# fieldkit-upper.net
KiCad netlist of a schematic drawn in EAGLE
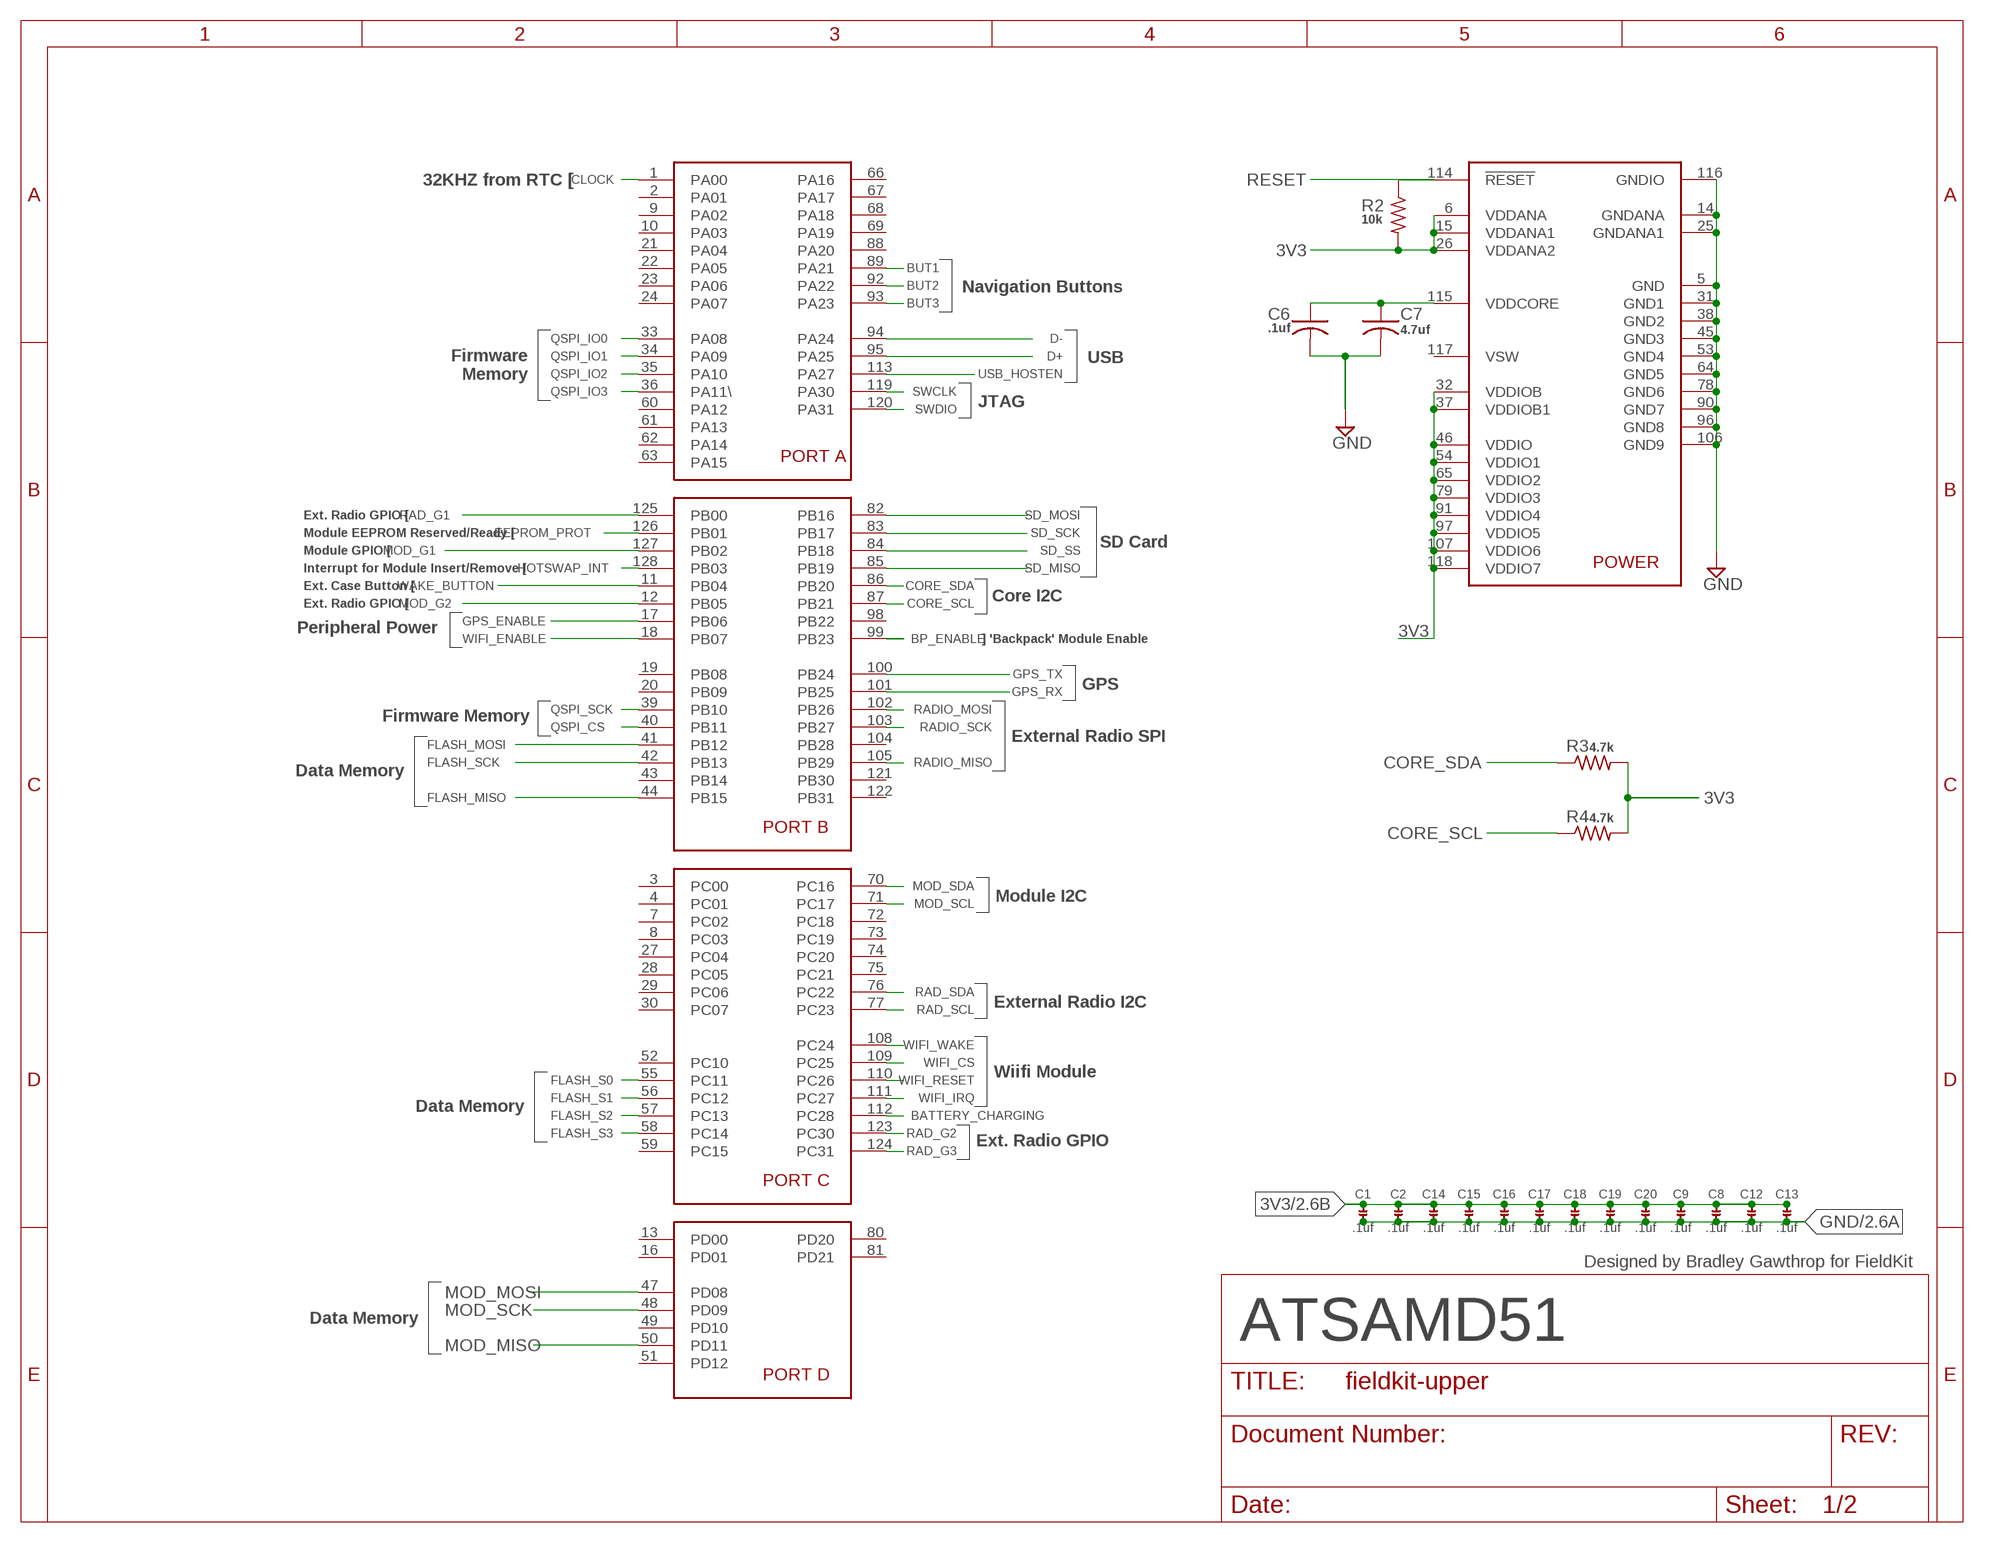
[diagram p0: schematic, sheet 1]
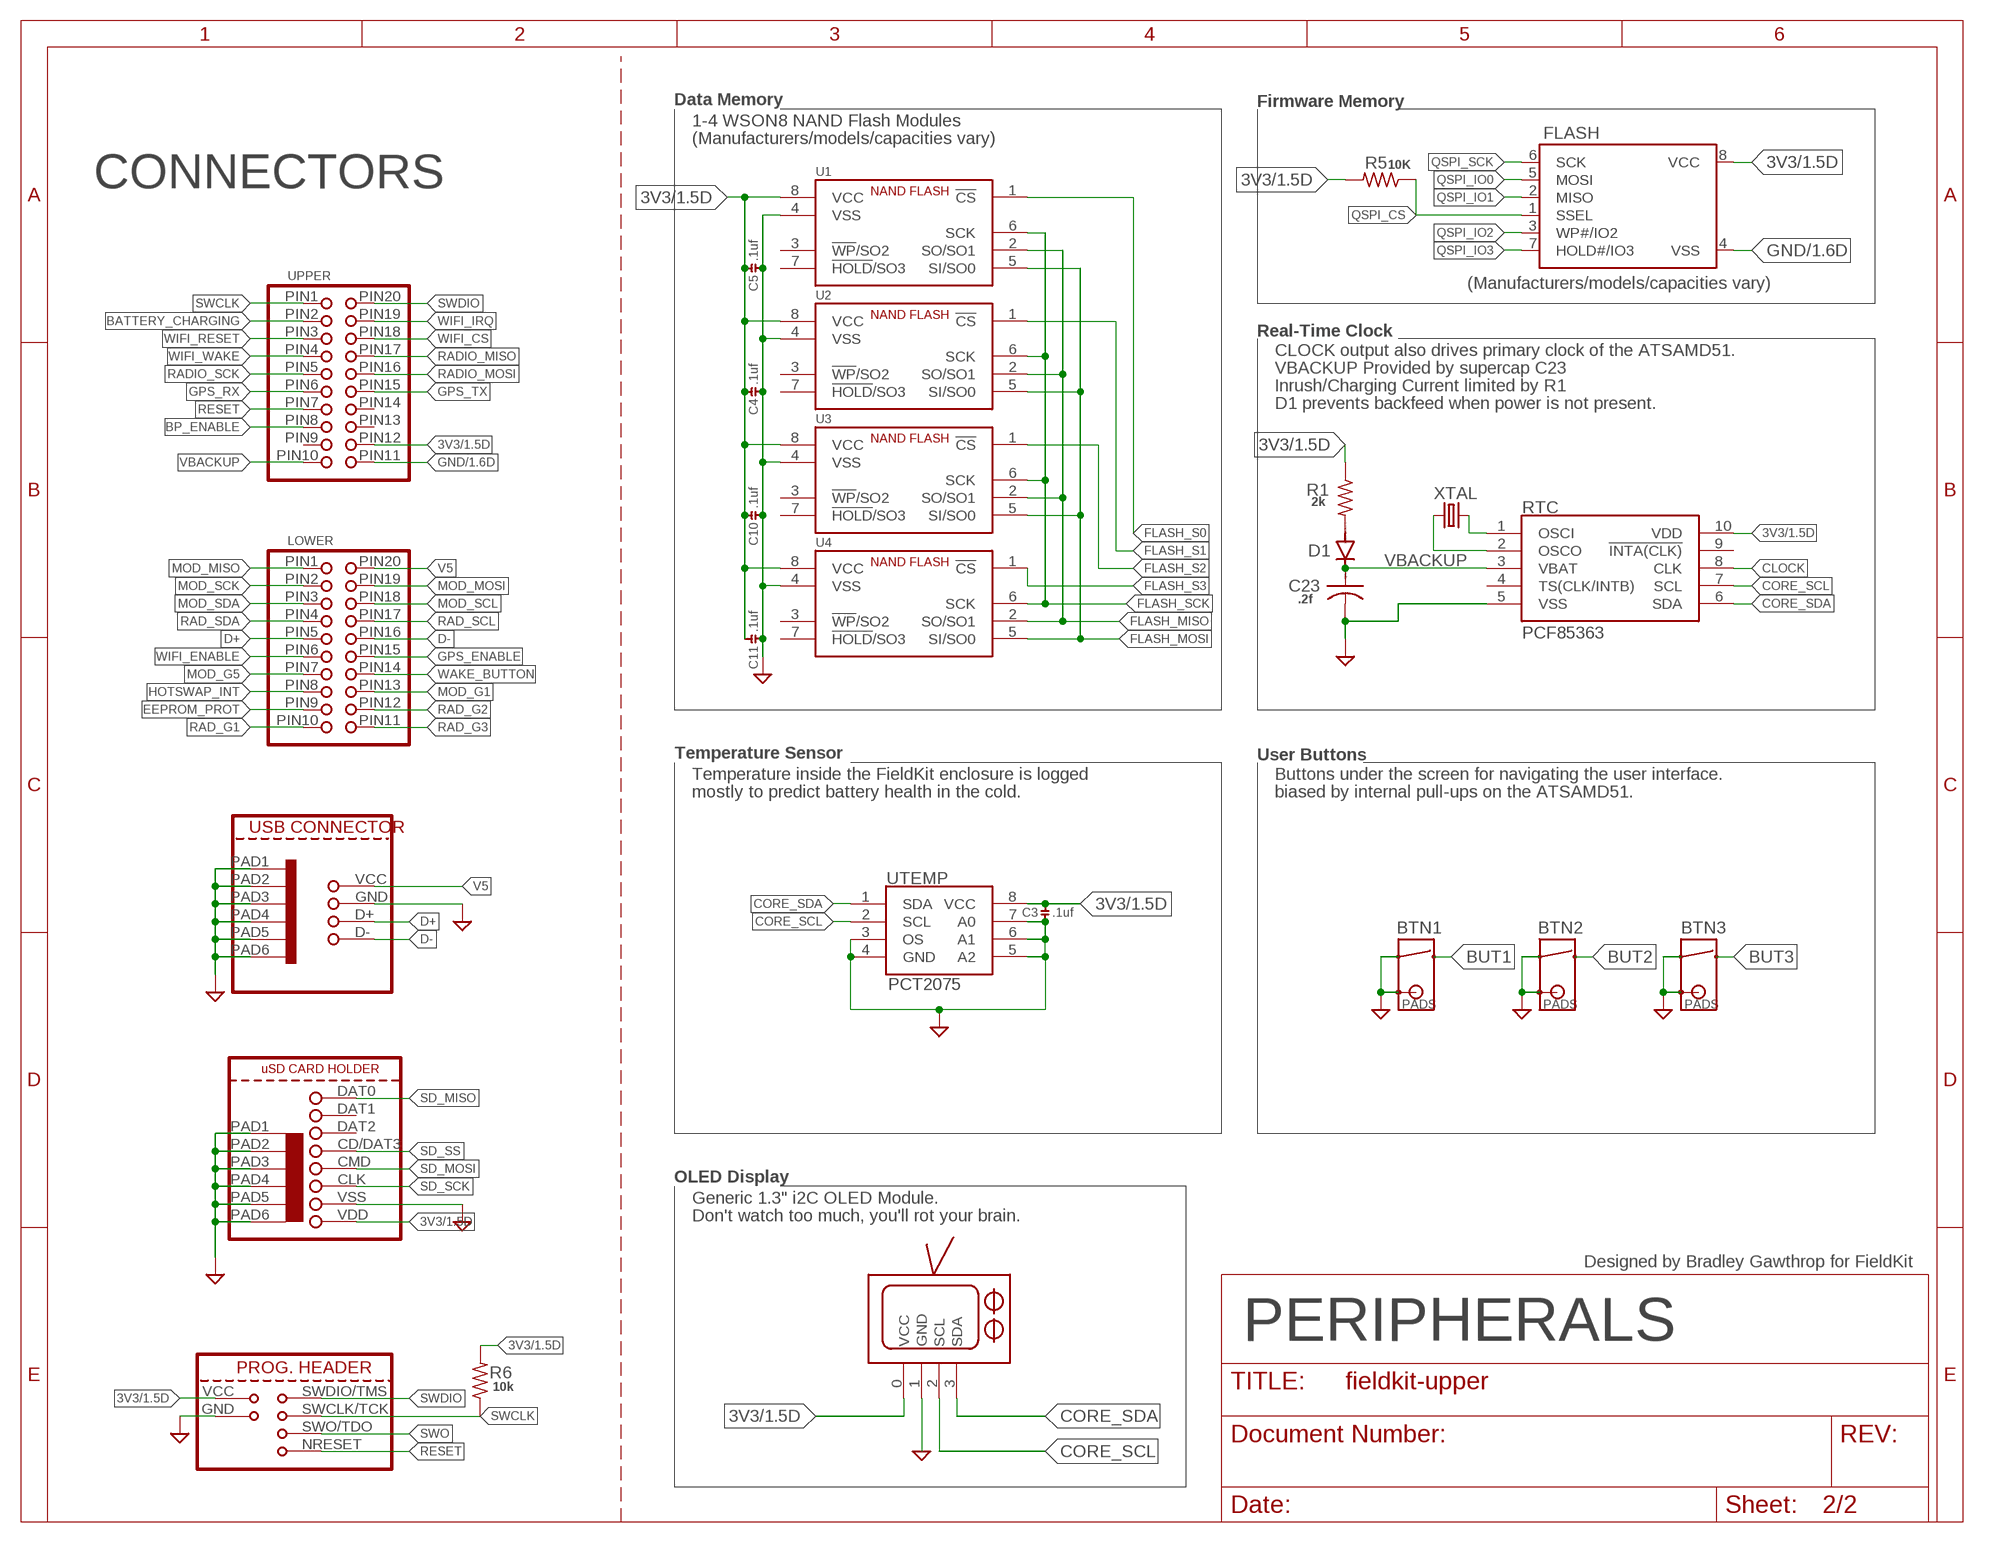
[diagram p1: schematic, sheet 2]

(export (version "E")
  (design (tool "Eeschema 10.0.6"))
  (components
    (comp (ref "BRAIN")
      (value "SAMD51PXXA")
      (footprint "eagle-import:SQFP-S-14X14-128")
      (libsource (lib "eagle-import") (part "SAMD51PXXA"))
    )
    (comp (ref "C1")
      (value ".1uf")
      (footprint "eagle-import:C0603K")
      (libsource (lib "eagle-import") (part "DCAP"))
    )
    (comp (ref "C2")
      (value ".1uf")
      (footprint "eagle-import:C0603K")
      (libsource (lib "eagle-import") (part "DCAP"))
    )
    (comp (ref "C6")
      (value ".1uf")
      (footprint "eagle-import:C0603K")
      (libsource (lib "eagle-import") (part "C-USC0603K"))
    )
    (comp (ref "C7")
      (value "4.7uf")
      (footprint "eagle-import:C0603K")
      (libsource (lib "eagle-import") (part "C-USC0603K"))
    )
    (comp (ref "C8")
      (value ".1uf")
      (footprint "eagle-import:C0603K")
      (libsource (lib "eagle-import") (part "DCAP"))
    )
    (comp (ref "C9")
      (value ".1uf")
      (footprint "eagle-import:C0603K")
      (libsource (lib "eagle-import") (part "DCAP"))
    )
    (comp (ref "C12")
      (value ".1uf")
      (footprint "eagle-import:C0603K")
      (libsource (lib "eagle-import") (part "DCAP"))
    )
    (comp (ref "C13")
      (value ".1uf")
      (footprint "eagle-import:C0603K")
      (libsource (lib "eagle-import") (part "DCAP"))
    )
    (comp (ref "C14")
      (value ".1uf")
      (footprint "eagle-import:C0603K")
      (libsource (lib "eagle-import") (part "DCAP"))
    )
    (comp (ref "C15")
      (value ".1uf")
      (footprint "eagle-import:C0603K")
      (libsource (lib "eagle-import") (part "DCAP"))
    )
    (comp (ref "C16")
      (value ".1uf")
      (footprint "eagle-import:C0603K")
      (libsource (lib "eagle-import") (part "DCAP"))
    )
    (comp (ref "C17")
      (value ".1uf")
      (footprint "eagle-import:C0603K")
      (libsource (lib "eagle-import") (part "DCAP"))
    )
    (comp (ref "C18")
      (value ".1uf")
      (footprint "eagle-import:C0603K")
      (libsource (lib "eagle-import") (part "DCAP"))
    )
    (comp (ref "C19")
      (value ".1uf")
      (footprint "eagle-import:C0603K")
      (libsource (lib "eagle-import") (part "DCAP"))
    )
    (comp (ref "C20")
      (value ".1uf")
      (footprint "eagle-import:C0603K")
      (libsource (lib "eagle-import") (part "DCAP"))
    )
    (comp (ref "R2")
      (value "10k")
      (footprint "eagle-import:R0603")
      (libsource (lib "eagle-import") (part "R-US_R0603"))
    )
    (comp (ref "R3")
      (value "4.7k")
      (footprint "eagle-import:R0603")
      (libsource (lib "eagle-import") (part "R-US_R0603"))
    )
    (comp (ref "R4")
      (value "4.7k")
      (footprint "eagle-import:R0603")
      (libsource (lib "eagle-import") (part "R-US_R0603"))
    )
    (comp (ref "BTN1")
      (value "SKRTLAE010")
      (footprint "eagle-import:SKRTLAE010")
      (libsource (lib "eagle-import") (part "SKRTLAE010"))
    )
    (comp (ref "BTN2")
      (value "SKRTLAE010")
      (footprint "eagle-import:SKRTLAE010")
      (libsource (lib "eagle-import") (part "SKRTLAE010"))
    )
    (comp (ref "BTN3")
      (value "SKRTLAE010")
      (footprint "eagle-import:SKRTLAE010")
      (libsource (lib "eagle-import") (part "SKRTLAE010"))
    )
    (comp (ref "C3")
      (value ".1uf")
      (footprint "eagle-import:C0603K")
      (libsource (lib "eagle-import") (part "DCAP"))
    )
    (comp (ref "C4")
      (value ".1uf")
      (footprint "eagle-import:C0603K")
      (libsource (lib "eagle-import") (part "DCAP"))
    )
    (comp (ref "C5")
      (value ".1uf")
      (footprint "eagle-import:C0603K")
      (libsource (lib "eagle-import") (part "DCAP"))
    )
    (comp (ref "C10")
      (value ".1uf")
      (footprint "eagle-import:C0603K")
      (libsource (lib "eagle-import") (part "DCAP"))
    )
    (comp (ref "C11")
      (value ".1uf")
      (footprint "eagle-import:C0603K")
      (libsource (lib "eagle-import") (part "DCAP"))
    )
    (comp (ref "C23")
      (value ".2f")
      (footprint "eagle-import:SUPERCAP")
      (libsource (lib "eagle-import") (part "DSK-3R3H204T614-H2L"))
    )
    (comp (ref "D1")
      (value "VS-10BQ015HM3/5BT")
      (footprint "eagle-import:SMB")
      (libsource (lib "eagle-import") (part "DIODE-SMB"))
    )
    (comp (ref "FLASH")
      (value "SPIFLASH_SOIC8208MIL")
      (footprint "eagle-import:SOIC8_208MIL")
      (libsource (lib "eagle-import") (part "SPIFLASH_SOIC8208MIL"))
    )
    (comp (ref "J1")
      (value "TAG-CONNECT")
      (footprint "eagle-import:TC2030-IDC")
      (libsource (lib "eagle-import") (part "TAG-CONNECT"))
    )
    (comp (ref "LOWER")
      (value "MOLEX-15-91-2200F")
      (footprint "eagle-import:20PH-F")
      (libsource (lib "eagle-import") (part "MOLEX-15-91-2200F"))
    )
    (comp (ref "R1")
      (value "2k")
      (footprint "eagle-import:R0603")
      (libsource (lib "eagle-import") (part "R-US_R0603"))
    )
    (comp (ref "R5")
      (value "10K")
      (footprint "eagle-import:R0603")
      (libsource (lib "eagle-import") (part "R-US_R0603"))
    )
    (comp (ref "R6")
      (value "10k")
      (footprint "eagle-import:R0603")
      (libsource (lib "eagle-import") (part "R-US_R0603"))
    )
    (comp (ref "RTC")
      (value "PCF85363ATT")
      (footprint "eagle-import:SOP50P490X110-10")
      (libsource (lib "eagle-import") (part "PCF85363ATT"))
    )
    (comp (ref "SCREEN")
      (value "SCREEN")
      (footprint "eagle-import:SCREEN")
      (libsource (lib "eagle-import") (part "SCREEN"))
    )
    (comp (ref "SD")
      (value "DM3D-SF")
      (footprint "eagle-import:DM3D-SF")
      (libsource (lib "eagle-import") (part "DM3D-SF"))
    )
    (comp (ref "U1")
      (value "TC58CVG1S3HRAIG")
      (footprint "eagle-import:WSON8")
      (libsource (lib "eagle-import") (part "TC58CVG1S3HRAIG"))
    )
    (comp (ref "U2")
      (value "TC58CVG1S3HRAIG")
      (footprint "eagle-import:WSON8")
      (libsource (lib "eagle-import") (part "TC58CVG1S3HRAIG"))
    )
    (comp (ref "U3")
      (value "TC58CVG1S3HRAIG")
      (footprint "eagle-import:WSON8")
      (libsource (lib "eagle-import") (part "TC58CVG1S3HRAIG"))
    )
    (comp (ref "U4")
      (value "TC58CVG1S3HRAIG")
      (footprint "eagle-import:WSON8")
      (libsource (lib "eagle-import") (part "TC58CVG1S3HRAIG"))
    )
    (comp (ref "UPPER")
      (value "MOLEX-15-91-2200F")
      (footprint "eagle-import:20PH-F")
      (libsource (lib "eagle-import") (part "MOLEX-15-91-2200F"))
    )
    (comp (ref "USB")
      (value "MOLEX-47491-0001")
      (footprint "eagle-import:MOELX-47491-0001")
      (libsource (lib "eagle-import") (part "MOLEX-47491-0001"))
    )
    (comp (ref "UTEMP")
      (value "PCT2075")
      (footprint "eagle-import:SO8")
      (libsource (lib "eagle-import") (part "PCT2075"))
    )
    (comp (ref "XTAL")
      (value "ABS07W")
      (footprint "eagle-import:ABS07W")
      (libsource (lib "eagle-import") (part "ABS07W"))
    )
  )
  (nets
    (net (code "1") (name "3V3") (class "Default")
      (node (ref "BRAIN") (pin "107") (pinfunction "VDDIO6_107") (pintype "bidirectional"))
      (node (ref "BRAIN") (pin "118") (pinfunction "VDDIO7_118") (pintype "bidirectional"))
      (node (ref "BRAIN") (pin "15") (pinfunction "VDDANA1_15") (pintype "bidirectional"))
      (node (ref "BRAIN") (pin "26") (pinfunction "VDDANA2_26") (pintype "bidirectional"))
      (node (ref "BRAIN") (pin "32") (pinfunction "VDDIOB_32") (pintype "bidirectional"))
      (node (ref "BRAIN") (pin "37") (pinfunction "VDDIOB1_37") (pintype "bidirectional"))
      (node (ref "BRAIN") (pin "46") (pinfunction "VDDIO_46") (pintype "bidirectional"))
      (node (ref "BRAIN") (pin "54") (pinfunction "VDDIO1_54") (pintype "bidirectional"))
      (node (ref "BRAIN") (pin "6") (pinfunction "VDDANA_6") (pintype "bidirectional"))
      (node (ref "BRAIN") (pin "65") (pinfunction "VDDIO2_65") (pintype "bidirectional"))
      (node (ref "BRAIN") (pin "79") (pinfunction "VDDIO3_79") (pintype "bidirectional"))
      (node (ref "BRAIN") (pin "91") (pinfunction "VDDIO4_91") (pintype "bidirectional"))
      (node (ref "BRAIN") (pin "97") (pinfunction "VDDIO5_97") (pintype "bidirectional"))
      (node (ref "C1") (pin "1") (pinfunction "1_1") (pintype "bidirectional"))
      (node (ref "C10") (pin "1") (pinfunction "1_1") (pintype "bidirectional"))
      (node (ref "C11") (pin "1") (pinfunction "1_1") (pintype "bidirectional"))
      (node (ref "C12") (pin "1") (pinfunction "1_1") (pintype "bidirectional"))
      (node (ref "C13") (pin "1") (pinfunction "1_1") (pintype "bidirectional"))
      (node (ref "C14") (pin "1") (pinfunction "1_1") (pintype "bidirectional"))
      (node (ref "C15") (pin "1") (pinfunction "1_1") (pintype "bidirectional"))
      (node (ref "C16") (pin "1") (pinfunction "1_1") (pintype "bidirectional"))
      (node (ref "C17") (pin "1") (pinfunction "1_1") (pintype "bidirectional"))
      (node (ref "C18") (pin "1") (pinfunction "1_1") (pintype "bidirectional"))
      (node (ref "C19") (pin "1") (pinfunction "1_1") (pintype "bidirectional"))
      (node (ref "C2") (pin "1") (pinfunction "1_1") (pintype "bidirectional"))
      (node (ref "C20") (pin "1") (pinfunction "1_1") (pintype "bidirectional"))
      (node (ref "C3") (pin "1") (pinfunction "1_1") (pintype "bidirectional"))
      (node (ref "C4") (pin "1") (pinfunction "1_1") (pintype "bidirectional"))
      (node (ref "C5") (pin "1") (pinfunction "1_1") (pintype "bidirectional"))
      (node (ref "C8") (pin "1") (pinfunction "1_1") (pintype "bidirectional"))
      (node (ref "C9") (pin "1") (pinfunction "1_1") (pintype "bidirectional"))
      (node (ref "FLASH") (pin "8") (pinfunction "VCC_8") (pintype "bidirectional"))
      (node (ref "J1") (pin "VCC") (pinfunction "VCC_VCC") (pintype "bidirectional"))
      (node (ref "R1") (pin "1") (pinfunction "1_1") (pintype "passive"))
      (node (ref "R2") (pin "2") (pinfunction "2_2") (pintype "passive"))
      (node (ref "R3") (pin "2") (pinfunction "2_2") (pintype "passive"))
      (node (ref "R4") (pin "2") (pinfunction "2_2") (pintype "passive"))
      (node (ref "R5") (pin "2") (pinfunction "2_2") (pintype "passive"))
      (node (ref "R6") (pin "2") (pinfunction "2_2") (pintype "passive"))
      (node (ref "RTC") (pin "10") (pinfunction "VDD_10") (pintype "bidirectional"))
      (node (ref "SCREEN") (pin "0") (pinfunction "VCC_0") (pintype "bidirectional"))
      (node (ref "SD") (pin "VDD") (pinfunction "VDD_VDD") (pintype "bidirectional"))
      (node (ref "U1") (pin "8") (pinfunction "VCC_8") (pintype "bidirectional"))
      (node (ref "U2") (pin "8") (pinfunction "VCC_8") (pintype "bidirectional"))
      (node (ref "U3") (pin "8") (pinfunction "VCC_8") (pintype "bidirectional"))
      (node (ref "U4") (pin "8") (pinfunction "VCC_8") (pintype "bidirectional"))
      (node (ref "UPPER") (pin "PIN12") (pinfunction "PIN12_PIN12") (pintype "bidirectional"))
      (node (ref "UTEMP") (pin "8") (pinfunction "VCC_8") (pintype "bidirectional"))
    )
    (net (code "2") (name "BATTERY_CHARGING") (class "Default")
      (node (ref "BRAIN") (pin "112") (pinfunction "PC28_112") (pintype "bidirectional"))
      (node (ref "UPPER") (pin "PIN2") (pinfunction "PIN2_PIN2") (pintype "bidirectional"))
    )
    (net (code "3") (name "BP_ENABLE") (class "Default")
      (node (ref "BRAIN") (pin "99") (pinfunction "PB23_99") (pintype "bidirectional"))
      (node (ref "UPPER") (pin "PIN8") (pinfunction "PIN8_PIN8") (pintype "bidirectional"))
    )
    (net (code "4") (name "BUT1") (class "Default")
      (node (ref "BRAIN") (pin "89") (pinfunction "PA21_89") (pintype "bidirectional"))
      (node (ref "BTN1") (pin "B") (pinfunction "2_B") (pintype "passive"))
    )
    (net (code "5") (name "BUT2") (class "Default")
      (node (ref "BRAIN") (pin "92") (pinfunction "PA22_92") (pintype "bidirectional"))
      (node (ref "BTN2") (pin "B") (pinfunction "2_B") (pintype "passive"))
    )
    (net (code "6") (name "BUT3") (class "Default")
      (node (ref "BRAIN") (pin "93") (pinfunction "PA23_93") (pintype "bidirectional"))
      (node (ref "BTN3") (pin "B") (pinfunction "2_B") (pintype "passive"))
    )
    (net (code "7") (name "CLOCK") (class "Default")
      (node (ref "BRAIN") (pin "1") (pinfunction "PA00_1") (pintype "bidirectional"))
      (node (ref "RTC") (pin "8") (pinfunction "CLK_8") (pintype "bidirectional"))
    )
    (net (code "8") (name "CORE_SCL") (class "Default")
      (node (ref "BRAIN") (pin "87") (pinfunction "PB21_87") (pintype "bidirectional"))
      (node (ref "R4") (pin "1") (pinfunction "1_1") (pintype "passive"))
      (node (ref "RTC") (pin "7") (pinfunction "SCL_7") (pintype "bidirectional"))
      (node (ref "SCREEN") (pin "2") (pinfunction "SCL_2") (pintype "bidirectional"))
      (node (ref "UTEMP") (pin "2") (pinfunction "SCL_2") (pintype "bidirectional"))
    )
    (net (code "9") (name "CORE_SDA") (class "Default")
      (node (ref "BRAIN") (pin "86") (pinfunction "PB20_86") (pintype "bidirectional"))
      (node (ref "R3") (pin "1") (pinfunction "1_1") (pintype "passive"))
      (node (ref "RTC") (pin "6") (pinfunction "SDA_6") (pintype "bidirectional"))
      (node (ref "SCREEN") (pin "3") (pinfunction "SDA_3") (pintype "bidirectional"))
      (node (ref "UTEMP") (pin "1") (pinfunction "SDA_1") (pintype "bidirectional"))
    )
    (net (code "10") (name "D+") (class "Default")
      (node (ref "BRAIN") (pin "95") (pinfunction "PA25_95") (pintype "bidirectional"))
      (node (ref "LOWER") (pin "PIN5") (pinfunction "PIN5_PIN5") (pintype "bidirectional"))
      (node (ref "USB") (pin "D+") (pinfunction "D+_D+") (pintype "bidirectional"))
    )
    (net (code "11") (name "D-") (class "Default")
      (node (ref "BRAIN") (pin "94") (pinfunction "PA24_94") (pintype "bidirectional"))
      (node (ref "LOWER") (pin "PIN16") (pinfunction "PIN16_PIN16") (pintype "bidirectional"))
      (node (ref "USB") (pin "D-") (pinfunction "D-_D-") (pintype "bidirectional"))
    )
    (net (code "12") (name "EEPROM_PROT") (class "Default")
      (node (ref "BRAIN") (pin "126") (pinfunction "PB01_126") (pintype "bidirectional"))
      (node (ref "LOWER") (pin "PIN9") (pinfunction "PIN9_PIN9") (pintype "bidirectional"))
    )
    (net (code "13") (name "FLASH_MISO") (class "Default")
      (node (ref "BRAIN") (pin "44") (pinfunction "PB15_44") (pintype "bidirectional"))
      (node (ref "U1") (pin "2") (pinfunction "SO/SO1_2") (pintype "bidirectional"))
      (node (ref "U2") (pin "2") (pinfunction "SO/SO1_2") (pintype "bidirectional"))
      (node (ref "U3") (pin "2") (pinfunction "SO/SO1_2") (pintype "bidirectional"))
      (node (ref "U4") (pin "2") (pinfunction "SO/SO1_2") (pintype "bidirectional"))
    )
    (net (code "14") (name "FLASH_MOSI") (class "Default")
      (node (ref "BRAIN") (pin "41") (pinfunction "PB12_41") (pintype "bidirectional"))
      (node (ref "U1") (pin "5") (pinfunction "SI/SO0_5") (pintype "bidirectional"))
      (node (ref "U2") (pin "5") (pinfunction "SI/SO0_5") (pintype "bidirectional"))
      (node (ref "U3") (pin "5") (pinfunction "SI/SO0_5") (pintype "bidirectional"))
      (node (ref "U4") (pin "5") (pinfunction "SI/SO0_5") (pintype "bidirectional"))
    )
    (net (code "15") (name "FLASH_S0") (class "Default")
      (node (ref "BRAIN") (pin "55") (pinfunction "PC11_55") (pintype "bidirectional"))
      (node (ref "U1") (pin "1") (pinfunction "~{CS}_1") (pintype "bidirectional"))
    )
    (net (code "16") (name "FLASH_S1") (class "Default")
      (node (ref "BRAIN") (pin "56") (pinfunction "PC12_56") (pintype "bidirectional"))
      (node (ref "U2") (pin "1") (pinfunction "~{CS}_1") (pintype "bidirectional"))
    )
    (net (code "17") (name "FLASH_S2") (class "Default")
      (node (ref "BRAIN") (pin "57") (pinfunction "PC13_57") (pintype "bidirectional"))
      (node (ref "U3") (pin "1") (pinfunction "~{CS}_1") (pintype "bidirectional"))
    )
    (net (code "18") (name "FLASH_S3") (class "Default")
      (node (ref "BRAIN") (pin "58") (pinfunction "PC14_58") (pintype "bidirectional"))
      (node (ref "U4") (pin "1") (pinfunction "~{CS}_1") (pintype "bidirectional"))
    )
    (net (code "19") (name "FLASH_SCK") (class "Default")
      (node (ref "BRAIN") (pin "42") (pinfunction "PB13_42") (pintype "bidirectional"))
      (node (ref "U1") (pin "6") (pinfunction "SCK_6") (pintype "bidirectional"))
      (node (ref "U2") (pin "6") (pinfunction "SCK_6") (pintype "bidirectional"))
      (node (ref "U3") (pin "6") (pinfunction "SCK_6") (pintype "bidirectional"))
      (node (ref "U4") (pin "6") (pinfunction "SCK_6") (pintype "bidirectional"))
    )
    (net (code "20") (name "GND") (class "Default")
      (node (ref "BRAIN") (pin "106") (pinfunction "GND9_106") (pintype "bidirectional"))
      (node (ref "BRAIN") (pin "116") (pinfunction "GNDIO_116") (pintype "bidirectional"))
      (node (ref "BRAIN") (pin "14") (pinfunction "GNDANA_14") (pintype "bidirectional"))
      (node (ref "BRAIN") (pin "25") (pinfunction "GNDANA1_25") (pintype "bidirectional"))
      (node (ref "BRAIN") (pin "31") (pinfunction "GND1_31") (pintype "bidirectional"))
      (node (ref "BRAIN") (pin "38") (pinfunction "GND2_38") (pintype "bidirectional"))
      (node (ref "BRAIN") (pin "45") (pinfunction "GND3_45") (pintype "bidirectional"))
      (node (ref "BRAIN") (pin "5") (pinfunction "GND_5") (pintype "bidirectional"))
      (node (ref "BRAIN") (pin "53") (pinfunction "GND4_53") (pintype "bidirectional"))
      (node (ref "BRAIN") (pin "64") (pinfunction "GND5_64") (pintype "bidirectional"))
      (node (ref "BRAIN") (pin "78") (pinfunction "GND6_78") (pintype "bidirectional"))
      (node (ref "BRAIN") (pin "90") (pinfunction "GND7_90") (pintype "bidirectional"))
      (node (ref "BRAIN") (pin "96") (pinfunction "GND8_96") (pintype "bidirectional"))
      (node (ref "BTN1") (pin "A") (pinfunction "1_A") (pintype "passive"))
      (node (ref "BTN1") (pin "A2") (pinfunction "1_A2") (pintype "passive"))
      (node (ref "BTN1") (pin "TAB") (pinfunction "PADS_TAB") (pintype "bidirectional"))
      (node (ref "BTN1") (pin "TAB2") (pinfunction "PADS_TAB2") (pintype "bidirectional"))
      (node (ref "BTN2") (pin "A") (pinfunction "1_A") (pintype "passive"))
      (node (ref "BTN2") (pin "A2") (pinfunction "1_A2") (pintype "passive"))
      (node (ref "BTN2") (pin "TAB") (pinfunction "PADS_TAB") (pintype "bidirectional"))
      (node (ref "BTN2") (pin "TAB2") (pinfunction "PADS_TAB2") (pintype "bidirectional"))
      (node (ref "BTN3") (pin "A") (pinfunction "1_A") (pintype "passive"))
      (node (ref "BTN3") (pin "A2") (pinfunction "1_A2") (pintype "passive"))
      (node (ref "BTN3") (pin "TAB") (pinfunction "PADS_TAB") (pintype "bidirectional"))
      (node (ref "BTN3") (pin "TAB2") (pinfunction "PADS_TAB2") (pintype "bidirectional"))
      (node (ref "C1") (pin "2") (pinfunction "2_2") (pintype "bidirectional"))
      (node (ref "C10") (pin "2") (pinfunction "2_2") (pintype "bidirectional"))
      (node (ref "C11") (pin "2") (pinfunction "2_2") (pintype "bidirectional"))
      (node (ref "C12") (pin "2") (pinfunction "2_2") (pintype "bidirectional"))
      (node (ref "C13") (pin "2") (pinfunction "2_2") (pintype "bidirectional"))
      (node (ref "C14") (pin "2") (pinfunction "2_2") (pintype "bidirectional"))
      (node (ref "C15") (pin "2") (pinfunction "2_2") (pintype "bidirectional"))
      (node (ref "C16") (pin "2") (pinfunction "2_2") (pintype "bidirectional"))
      (node (ref "C17") (pin "2") (pinfunction "2_2") (pintype "bidirectional"))
      (node (ref "C18") (pin "2") (pinfunction "2_2") (pintype "bidirectional"))
      (node (ref "C19") (pin "2") (pinfunction "2_2") (pintype "bidirectional"))
      (node (ref "C2") (pin "2") (pinfunction "2_2") (pintype "bidirectional"))
      (node (ref "C20") (pin "2") (pinfunction "2_2") (pintype "bidirectional"))
      (node (ref "C23") (pin "-") (pinfunction "-_-") (pintype "passive"))
      (node (ref "C3") (pin "2") (pinfunction "2_2") (pintype "bidirectional"))
      (node (ref "C4") (pin "2") (pinfunction "2_2") (pintype "bidirectional"))
      (node (ref "C5") (pin "2") (pinfunction "2_2") (pintype "bidirectional"))
      (node (ref "C6") (pin "2") (pinfunction "2_2") (pintype "passive"))
      (node (ref "C7") (pin "2") (pinfunction "2_2") (pintype "passive"))
      (node (ref "C8") (pin "2") (pinfunction "2_2") (pintype "bidirectional"))
      (node (ref "C9") (pin "2") (pinfunction "2_2") (pintype "bidirectional"))
      (node (ref "FLASH") (pin "4") (pinfunction "VSS_4") (pintype "bidirectional"))
      (node (ref "J1") (pin "GND") (pinfunction "GND_GND") (pintype "bidirectional"))
      (node (ref "RTC") (pin "5") (pinfunction "VSS_5") (pintype "bidirectional"))
      (node (ref "SCREEN") (pin "1") (pinfunction "GND_1") (pintype "bidirectional"))
      (node (ref "SD") (pin "PAD1") (pinfunction "PAD1_PAD1") (pintype "bidirectional"))
      (node (ref "SD") (pin "PAD2") (pinfunction "PAD2_PAD2") (pintype "bidirectional"))
      (node (ref "SD") (pin "PAD3") (pinfunction "PAD3_PAD3") (pintype "bidirectional"))
      (node (ref "SD") (pin "PAD4") (pinfunction "PAD4_PAD4") (pintype "bidirectional"))
      (node (ref "SD") (pin "PAD5") (pinfunction "PAD5_PAD5") (pintype "bidirectional"))
      (node (ref "SD") (pin "PAD6") (pinfunction "PAD6_PAD6") (pintype "bidirectional"))
      (node (ref "SD") (pin "VSS") (pinfunction "VSS_VSS") (pintype "bidirectional"))
      (node (ref "U1") (pin "4") (pinfunction "VSS_4") (pintype "bidirectional"))
      (node (ref "U2") (pin "4") (pinfunction "VSS_4") (pintype "bidirectional"))
      (node (ref "U3") (pin "4") (pinfunction "VSS_4") (pintype "bidirectional"))
      (node (ref "U4") (pin "4") (pinfunction "VSS_4") (pintype "bidirectional"))
      (node (ref "UPPER") (pin "PIN11") (pinfunction "PIN11_PIN11") (pintype "bidirectional"))
      (node (ref "USB") (pin "GND") (pinfunction "GND_GND") (pintype "bidirectional"))
      (node (ref "USB") (pin "PAD1") (pinfunction "PAD1_PAD1") (pintype "bidirectional"))
      (node (ref "USB") (pin "PAD2") (pinfunction "PAD2_PAD2") (pintype "bidirectional"))
      (node (ref "USB") (pin "PAD3") (pinfunction "PAD3_PAD3") (pintype "bidirectional"))
      (node (ref "USB") (pin "PAD4") (pinfunction "PAD4_PAD4") (pintype "bidirectional"))
      (node (ref "USB") (pin "PAD5") (pinfunction "PAD5_PAD5") (pintype "bidirectional"))
      (node (ref "USB") (pin "PAD6") (pinfunction "PAD6_PAD6") (pintype "bidirectional"))
      (node (ref "UTEMP") (pin "3") (pinfunction "OS_3") (pintype "bidirectional"))
      (node (ref "UTEMP") (pin "4") (pinfunction "GND_4") (pintype "bidirectional"))
      (node (ref "UTEMP") (pin "5") (pinfunction "A2_5") (pintype "bidirectional"))
      (node (ref "UTEMP") (pin "6") (pinfunction "A1_6") (pintype "bidirectional"))
      (node (ref "UTEMP") (pin "7") (pinfunction "A0_7") (pintype "bidirectional"))
    )
    (net (code "21") (name "GPS_ENABLE") (class "Default")
      (node (ref "BRAIN") (pin "17") (pinfunction "PB06_17") (pintype "bidirectional"))
      (node (ref "LOWER") (pin "PIN15") (pinfunction "PIN15_PIN15") (pintype "bidirectional"))
    )
    (net (code "22") (name "GPS_RX") (class "Default")
      (node (ref "BRAIN") (pin "101") (pinfunction "PB25_101") (pintype "bidirectional"))
      (node (ref "UPPER") (pin "PIN6") (pinfunction "PIN6_PIN6") (pintype "bidirectional"))
    )
    (net (code "23") (name "GPS_TX") (class "Default")
      (node (ref "BRAIN") (pin "100") (pinfunction "PB24_100") (pintype "bidirectional"))
      (node (ref "UPPER") (pin "PIN15") (pinfunction "PIN15_PIN15") (pintype "bidirectional"))
    )
    (net (code "24") (name "HOTSWAP_INT") (class "Default")
      (node (ref "BRAIN") (pin "128") (pinfunction "PB03_128") (pintype "bidirectional"))
      (node (ref "LOWER") (pin "PIN8") (pinfunction "PIN8_PIN8") (pintype "bidirectional"))
    )
    (net (code "25") (name "MOD_G1") (class "Default")
      (node (ref "BRAIN") (pin "127") (pinfunction "PB02_127") (pintype "bidirectional"))
      (node (ref "LOWER") (pin "PIN13") (pinfunction "PIN13_PIN13") (pintype "bidirectional"))
    )
    (net (code "26") (name "MOD_G2") (class "Default")
      (node (ref "BRAIN") (pin "12") (pinfunction "PB05_12") (pintype "bidirectional"))
    )
    (net (code "27") (name "MOD_G5") (class "Default")
      (node (ref "LOWER") (pin "PIN7") (pinfunction "PIN7_PIN7") (pintype "bidirectional"))
    )
    (net (code "28") (name "MOD_MISO") (class "Default")
      (node (ref "BRAIN") (pin "50") (pinfunction "PD11_50") (pintype "bidirectional"))
      (node (ref "LOWER") (pin "PIN1") (pinfunction "PIN1_PIN1") (pintype "bidirectional"))
    )
    (net (code "29") (name "MOD_MOSI") (class "Default")
      (node (ref "BRAIN") (pin "47") (pinfunction "PD08_47") (pintype "bidirectional"))
      (node (ref "LOWER") (pin "PIN19") (pinfunction "PIN19_PIN19") (pintype "bidirectional"))
    )
    (net (code "30") (name "MOD_SCK") (class "Default")
      (node (ref "BRAIN") (pin "48") (pinfunction "PD09_48") (pintype "bidirectional"))
      (node (ref "LOWER") (pin "PIN2") (pinfunction "PIN2_PIN2") (pintype "bidirectional"))
    )
    (net (code "31") (name "MOD_SCL") (class "Default")
      (node (ref "BRAIN") (pin "71") (pinfunction "PC17_71") (pintype "bidirectional"))
      (node (ref "LOWER") (pin "PIN18") (pinfunction "PIN18_PIN18") (pintype "bidirectional"))
    )
    (net (code "32") (name "MOD_SDA") (class "Default")
      (node (ref "BRAIN") (pin "70") (pinfunction "PC16_70") (pintype "bidirectional"))
      (node (ref "LOWER") (pin "PIN3") (pinfunction "PIN3_PIN3") (pintype "bidirectional"))
    )
    (net (code "33") (name "Net-(BRAINE-VDDCORE)") (class "Default")
      (node (ref "BRAIN") (pin "115") (pinfunction "VDDCORE_115") (pintype "bidirectional"))
      (node (ref "C6") (pin "1") (pinfunction "1_1") (pintype "passive"))
      (node (ref "C7") (pin "1") (pinfunction "1_1") (pintype "passive"))
    )
    (net (code "34") (name "Net-(D1-PadA)") (class "Default")
      (node (ref "D1") (pin "A") (pinfunction "A_A") (pintype "passive"))
      (node (ref "R1") (pin "2") (pinfunction "2_2") (pintype "passive"))
    )
    (net (code "35") (name "Net-(RTC-OSCI)") (class "Default")
      (node (ref "RTC") (pin "1") (pinfunction "OSCI_1") (pintype "bidirectional"))
      (node (ref "XTAL") (pin "P$2") (pinfunction "2_P$2") (pintype "passive"))
    )
    (net (code "36") (name "Net-(RTC-OSCO)") (class "Default")
      (node (ref "RTC") (pin "2") (pinfunction "OSCO_2") (pintype "bidirectional"))
      (node (ref "XTAL") (pin "P$1") (pinfunction "1_P$1") (pintype "passive"))
    )
    (net (code "37") (name "QSPI_CS") (class "Default")
      (node (ref "BRAIN") (pin "40") (pinfunction "PB11_40") (pintype "bidirectional"))
      (node (ref "FLASH") (pin "1") (pinfunction "SSEL_1") (pintype "bidirectional"))
      (node (ref "R5") (pin "1") (pinfunction "1_1") (pintype "passive"))
    )
    (net (code "38") (name "QSPI_IO0") (class "Default")
      (node (ref "BRAIN") (pin "33") (pinfunction "PA08_33") (pintype "bidirectional"))
      (node (ref "FLASH") (pin "5") (pinfunction "MOSI_5") (pintype "bidirectional"))
    )
    (net (code "39") (name "QSPI_IO1") (class "Default")
      (node (ref "BRAIN") (pin "34") (pinfunction "PA09_34") (pintype "bidirectional"))
      (node (ref "FLASH") (pin "2") (pinfunction "MISO_2") (pintype "bidirectional"))
    )
    (net (code "40") (name "QSPI_IO2") (class "Default")
      (node (ref "BRAIN") (pin "35") (pinfunction "PA10_35") (pintype "bidirectional"))
      (node (ref "FLASH") (pin "3") (pinfunction "WP#/IO2_3") (pintype "bidirectional"))
    )
    (net (code "41") (name "QSPI_IO3") (class "Default")
      (node (ref "BRAIN") (pin "36") (pinfunction "PA11\\_36") (pintype "bidirectional"))
      (node (ref "FLASH") (pin "7") (pinfunction "HOLD#/IO3_7") (pintype "bidirectional"))
    )
    (net (code "42") (name "QSPI_SCK") (class "Default")
      (node (ref "BRAIN") (pin "39") (pinfunction "PB10_39") (pintype "bidirectional"))
      (node (ref "FLASH") (pin "6") (pinfunction "SCK_6") (pintype "bidirectional"))
    )
    (net (code "43") (name "RADIO_MISO") (class "Default")
      (node (ref "BRAIN") (pin "105") (pinfunction "PB29_105") (pintype "bidirectional"))
      (node (ref "UPPER") (pin "PIN17") (pinfunction "PIN17_PIN17") (pintype "bidirectional"))
    )
    (net (code "44") (name "RADIO_MOSI") (class "Default")
      (node (ref "BRAIN") (pin "102") (pinfunction "PB26_102") (pintype "bidirectional"))
      (node (ref "UPPER") (pin "PIN16") (pinfunction "PIN16_PIN16") (pintype "bidirectional"))
    )
    (net (code "45") (name "RADIO_SCK") (class "Default")
      (node (ref "BRAIN") (pin "103") (pinfunction "PB27_103") (pintype "bidirectional"))
      (node (ref "UPPER") (pin "PIN5") (pinfunction "PIN5_PIN5") (pintype "bidirectional"))
    )
    (net (code "46") (name "RAD_G1") (class "Default")
      (node (ref "BRAIN") (pin "125") (pinfunction "PB00_125") (pintype "bidirectional"))
      (node (ref "LOWER") (pin "PIN10") (pinfunction "PIN10_PIN10") (pintype "bidirectional"))
    )
    (net (code "47") (name "RAD_G2") (class "Default")
      (node (ref "BRAIN") (pin "123") (pinfunction "PC30_123") (pintype "bidirectional"))
      (node (ref "LOWER") (pin "PIN12") (pinfunction "PIN12_PIN12") (pintype "bidirectional"))
    )
    (net (code "48") (name "RAD_G3") (class "Default")
      (node (ref "BRAIN") (pin "124") (pinfunction "PC31_124") (pintype "bidirectional"))
      (node (ref "LOWER") (pin "PIN11") (pinfunction "PIN11_PIN11") (pintype "bidirectional"))
    )
    (net (code "49") (name "RAD_SCL") (class "Default")
      (node (ref "BRAIN") (pin "77") (pinfunction "PC23_77") (pintype "bidirectional"))
      (node (ref "LOWER") (pin "PIN17") (pinfunction "PIN17_PIN17") (pintype "bidirectional"))
    )
    (net (code "50") (name "RAD_SDA") (class "Default")
      (node (ref "BRAIN") (pin "76") (pinfunction "PC22_76") (pintype "bidirectional"))
      (node (ref "LOWER") (pin "PIN4") (pinfunction "PIN4_PIN4") (pintype "bidirectional"))
    )
    (net (code "51") (name "RESET") (class "Default")
      (node (ref "BRAIN") (pin "114") (pinfunction "~{RESET}_114") (pintype "bidirectional"))
      (node (ref "J1") (pin "NRESET") (pinfunction "RESET_NRESET") (pintype "bidirectional"))
      (node (ref "R2") (pin "1") (pinfunction "1_1") (pintype "passive"))
      (node (ref "UPPER") (pin "PIN7") (pinfunction "PIN7_PIN7") (pintype "bidirectional"))
    )
    (net (code "52") (name "SD_MISO") (class "Default")
      (node (ref "BRAIN") (pin "85") (pinfunction "PB19_85") (pintype "bidirectional"))
      (node (ref "SD") (pin "DAT0") (pinfunction "DAT0_DAT0") (pintype "bidirectional"))
    )
    (net (code "53") (name "SD_MOSI") (class "Default")
      (node (ref "BRAIN") (pin "82") (pinfunction "PB16_82") (pintype "bidirectional"))
      (node (ref "SD") (pin "CMD") (pinfunction "CMD_CMD") (pintype "bidirectional"))
    )
    (net (code "54") (name "SD_SCK") (class "Default")
      (node (ref "BRAIN") (pin "83") (pinfunction "PB17_83") (pintype "bidirectional"))
      (node (ref "SD") (pin "CLK") (pinfunction "CLK_CLK") (pintype "bidirectional"))
    )
    (net (code "55") (name "SD_SS") (class "Default")
      (node (ref "BRAIN") (pin "84") (pinfunction "PB18_84") (pintype "bidirectional"))
      (node (ref "SD") (pin "CD/DAT3") (pinfunction "DAT3_CD/DAT3") (pintype "bidirectional"))
    )
    (net (code "56") (name "SWCLK") (class "Default")
      (node (ref "BRAIN") (pin "119") (pinfunction "PA30_119") (pintype "bidirectional"))
      (node (ref "J1") (pin "SWCLK/TCK") (pinfunction "SWCLK_SWCLK/TCK") (pintype "bidirectional"))
      (node (ref "R6") (pin "1") (pinfunction "1_1") (pintype "passive"))
      (node (ref "UPPER") (pin "PIN1") (pinfunction "PIN1_PIN1") (pintype "bidirectional"))
    )
    (net (code "57") (name "SWDIO") (class "Default")
      (node (ref "BRAIN") (pin "120") (pinfunction "PA31_120") (pintype "bidirectional"))
      (node (ref "J1") (pin "SWDIO/TMS") (pinfunction "SWDIO_SWDIO/TMS") (pintype "bidirectional"))
      (node (ref "UPPER") (pin "PIN20") (pinfunction "PIN20_PIN20") (pintype "bidirectional"))
    )
    (net (code "58") (name "SWO") (class "Default")
      (node (ref "J1") (pin "SWO/TDO") (pinfunction "SWO_SWO/TDO") (pintype "bidirectional"))
    )
    (net (code "59") (name "USB_HOSTEN") (class "Default")
      (node (ref "BRAIN") (pin "113") (pinfunction "PA27_113") (pintype "bidirectional"))
    )
    (net (code "60") (name "V5") (class "Default")
      (node (ref "LOWER") (pin "PIN20") (pinfunction "PIN20_PIN20") (pintype "bidirectional"))
      (node (ref "USB") (pin "VCC") (pinfunction "VBUS_VCC") (pintype "bidirectional"))
    )
    (net (code "61") (name "VBACKUP") (class "Default")
      (node (ref "C23") (pin "+") (pinfunction "+_+") (pintype "passive"))
      (node (ref "D1") (pin "C") (pinfunction "C_C") (pintype "passive"))
      (node (ref "RTC") (pin "3") (pinfunction "VBAT_3") (pintype "bidirectional"))
      (node (ref "UPPER") (pin "PIN10") (pinfunction "PIN10_PIN10") (pintype "bidirectional"))
    )
    (net (code "62") (name "WAKE_BUTTON") (class "Default")
      (node (ref "BRAIN") (pin "11") (pinfunction "PB04_11") (pintype "bidirectional"))
      (node (ref "LOWER") (pin "PIN14") (pinfunction "PIN14_PIN14") (pintype "bidirectional"))
    )
    (net (code "63") (name "WIFI_CS") (class "Default")
      (node (ref "BRAIN") (pin "109") (pinfunction "PC25_109") (pintype "bidirectional"))
      (node (ref "UPPER") (pin "PIN18") (pinfunction "PIN18_PIN18") (pintype "bidirectional"))
    )
    (net (code "64") (name "WIFI_ENABLE") (class "Default")
      (node (ref "BRAIN") (pin "18") (pinfunction "PB07_18") (pintype "bidirectional"))
      (node (ref "LOWER") (pin "PIN6") (pinfunction "PIN6_PIN6") (pintype "bidirectional"))
    )
    (net (code "65") (name "WIFI_IRQ") (class "Default")
      (node (ref "BRAIN") (pin "111") (pinfunction "PC27_111") (pintype "bidirectional"))
      (node (ref "UPPER") (pin "PIN19") (pinfunction "PIN19_PIN19") (pintype "bidirectional"))
    )
    (net (code "66") (name "WIFI_RESET") (class "Default")
      (node (ref "BRAIN") (pin "110") (pinfunction "PC26_110") (pintype "bidirectional"))
      (node (ref "UPPER") (pin "PIN3") (pinfunction "PIN3_PIN3") (pintype "bidirectional"))
    )
    (net (code "67") (name "WIFI_WAKE") (class "Default")
      (node (ref "BRAIN") (pin "108") (pinfunction "PC24_108") (pintype "bidirectional"))
      (node (ref "UPPER") (pin "PIN4") (pinfunction "PIN4_PIN4") (pintype "bidirectional"))
    )
    (net (code "68") (name "unconnected-(BRAINA-PA01-Pad2)") (class "Default")
      (node (ref "BRAIN") (pin "2") (pinfunction "PA01_2") (pintype "bidirectional"))
    )
    (net (code "69") (name "unconnected-(BRAINA-PA02-Pad9)") (class "Default")
      (node (ref "BRAIN") (pin "9") (pinfunction "PA02_9") (pintype "bidirectional"))
    )
    (net (code "70") (name "unconnected-(BRAINA-PA03-Pad10)") (class "Default")
      (node (ref "BRAIN") (pin "10") (pinfunction "PA03_10") (pintype "bidirectional"))
    )
    (net (code "71") (name "unconnected-(BRAINA-PA04-Pad21)") (class "Default")
      (node (ref "BRAIN") (pin "21") (pinfunction "PA04_21") (pintype "bidirectional"))
    )
    (net (code "72") (name "unconnected-(BRAINA-PA05-Pad22)") (class "Default")
      (node (ref "BRAIN") (pin "22") (pinfunction "PA05_22") (pintype "bidirectional"))
    )
    (net (code "73") (name "unconnected-(BRAINA-PA06-Pad23)") (class "Default")
      (node (ref "BRAIN") (pin "23") (pinfunction "PA06_23") (pintype "bidirectional"))
    )
    (net (code "74") (name "unconnected-(BRAINA-PA07-Pad24)") (class "Default")
      (node (ref "BRAIN") (pin "24") (pinfunction "PA07_24") (pintype "bidirectional"))
    )
    (net (code "75") (name "unconnected-(BRAINA-PA12-Pad60)") (class "Default")
      (node (ref "BRAIN") (pin "60") (pinfunction "PA12_60") (pintype "bidirectional"))
    )
    (net (code "76") (name "unconnected-(BRAINA-PA13-Pad61)") (class "Default")
      (node (ref "BRAIN") (pin "61") (pinfunction "PA13_61") (pintype "bidirectional"))
    )
    (net (code "77") (name "unconnected-(BRAINA-PA14-Pad62)") (class "Default")
      (node (ref "BRAIN") (pin "62") (pinfunction "PA14_62") (pintype "bidirectional"))
    )
    (net (code "78") (name "unconnected-(BRAINA-PA15-Pad63)") (class "Default")
      (node (ref "BRAIN") (pin "63") (pinfunction "PA15_63") (pintype "bidirectional"))
    )
    (net (code "79") (name "unconnected-(BRAINA-PA16-Pad66)") (class "Default")
      (node (ref "BRAIN") (pin "66") (pinfunction "PA16_66") (pintype "bidirectional"))
    )
    (net (code "80") (name "unconnected-(BRAINA-PA17-Pad67)") (class "Default")
      (node (ref "BRAIN") (pin "67") (pinfunction "PA17_67") (pintype "bidirectional"))
    )
    (net (code "81") (name "unconnected-(BRAINA-PA18-Pad68)") (class "Default")
      (node (ref "BRAIN") (pin "68") (pinfunction "PA18_68") (pintype "bidirectional"))
    )
    (net (code "82") (name "unconnected-(BRAINA-PA19-Pad69)") (class "Default")
      (node (ref "BRAIN") (pin "69") (pinfunction "PA19_69") (pintype "bidirectional"))
    )
    (net (code "83") (name "unconnected-(BRAINA-PA20-Pad88)") (class "Default")
      (node (ref "BRAIN") (pin "88") (pinfunction "PA20_88") (pintype "bidirectional"))
    )
    (net (code "84") (name "unconnected-(BRAINB-PB08-Pad19)") (class "Default")
      (node (ref "BRAIN") (pin "19") (pinfunction "PB08_19") (pintype "bidirectional"))
    )
    (net (code "85") (name "unconnected-(BRAINB-PB09-Pad20)") (class "Default")
      (node (ref "BRAIN") (pin "20") (pinfunction "PB09_20") (pintype "bidirectional"))
    )
    (net (code "86") (name "unconnected-(BRAINB-PB14-Pad43)") (class "Default")
      (node (ref "BRAIN") (pin "43") (pinfunction "PB14_43") (pintype "bidirectional"))
    )
    (net (code "87") (name "unconnected-(BRAINB-PB22-Pad98)") (class "Default")
      (node (ref "BRAIN") (pin "98") (pinfunction "PB22_98") (pintype "bidirectional"))
    )
    (net (code "88") (name "unconnected-(BRAINB-PB28-Pad104)") (class "Default")
      (node (ref "BRAIN") (pin "104") (pinfunction "PB28_104") (pintype "bidirectional"))
    )
    (net (code "89") (name "unconnected-(BRAINB-PB30-Pad121)") (class "Default")
      (node (ref "BRAIN") (pin "121") (pinfunction "PB30_121") (pintype "bidirectional"))
    )
    (net (code "90") (name "unconnected-(BRAINB-PB31-Pad122)") (class "Default")
      (node (ref "BRAIN") (pin "122") (pinfunction "PB31_122") (pintype "bidirectional"))
    )
    (net (code "91") (name "unconnected-(BRAINC-PC00-Pad3)") (class "Default")
      (node (ref "BRAIN") (pin "3") (pinfunction "PC00_3") (pintype "bidirectional"))
    )
    (net (code "92") (name "unconnected-(BRAINC-PC01-Pad4)") (class "Default")
      (node (ref "BRAIN") (pin "4") (pinfunction "PC01_4") (pintype "bidirectional"))
    )
    (net (code "93") (name "unconnected-(BRAINC-PC02-Pad7)") (class "Default")
      (node (ref "BRAIN") (pin "7") (pinfunction "PC02_7") (pintype "bidirectional"))
    )
    (net (code "94") (name "unconnected-(BRAINC-PC03-Pad8)") (class "Default")
      (node (ref "BRAIN") (pin "8") (pinfunction "PC03_8") (pintype "bidirectional"))
    )
    (net (code "95") (name "unconnected-(BRAINC-PC04-Pad27)") (class "Default")
      (node (ref "BRAIN") (pin "27") (pinfunction "PC04_27") (pintype "bidirectional"))
    )
    (net (code "96") (name "unconnected-(BRAINC-PC05-Pad28)") (class "Default")
      (node (ref "BRAIN") (pin "28") (pinfunction "PC05_28") (pintype "bidirectional"))
    )
    (net (code "97") (name "unconnected-(BRAINC-PC06-Pad29)") (class "Default")
      (node (ref "BRAIN") (pin "29") (pinfunction "PC06_29") (pintype "bidirectional"))
    )
    (net (code "98") (name "unconnected-(BRAINC-PC07-Pad30)") (class "Default")
      (node (ref "BRAIN") (pin "30") (pinfunction "PC07_30") (pintype "bidirectional"))
    )
    (net (code "99") (name "unconnected-(BRAINC-PC10-Pad52)") (class "Default")
      (node (ref "BRAIN") (pin "52") (pinfunction "PC10_52") (pintype "bidirectional"))
    )
    (net (code "100") (name "unconnected-(BRAINC-PC15-Pad59)") (class "Default")
      (node (ref "BRAIN") (pin "59") (pinfunction "PC15_59") (pintype "bidirectional"))
    )
    (net (code "101") (name "unconnected-(BRAINC-PC18-Pad72)") (class "Default")
      (node (ref "BRAIN") (pin "72") (pinfunction "PC18_72") (pintype "bidirectional"))
    )
    (net (code "102") (name "unconnected-(BRAINC-PC19-Pad73)") (class "Default")
      (node (ref "BRAIN") (pin "73") (pinfunction "PC19_73") (pintype "bidirectional"))
    )
    (net (code "103") (name "unconnected-(BRAINC-PC20-Pad74)") (class "Default")
      (node (ref "BRAIN") (pin "74") (pinfunction "PC20_74") (pintype "bidirectional"))
    )
    (net (code "104") (name "unconnected-(BRAINC-PC21-Pad75)") (class "Default")
      (node (ref "BRAIN") (pin "75") (pinfunction "PC21_75") (pintype "bidirectional"))
    )
    (net (code "105") (name "unconnected-(BRAIND-PD00-Pad13)") (class "Default")
      (node (ref "BRAIN") (pin "13") (pinfunction "PD00_13") (pintype "bidirectional"))
    )
    (net (code "106") (name "unconnected-(BRAIND-PD01-Pad16)") (class "Default")
      (node (ref "BRAIN") (pin "16") (pinfunction "PD01_16") (pintype "bidirectional"))
    )
    (net (code "107") (name "unconnected-(BRAIND-PD10-Pad49)") (class "Default")
      (node (ref "BRAIN") (pin "49") (pinfunction "PD10_49") (pintype "bidirectional"))
    )
    (net (code "108") (name "unconnected-(BRAIND-PD12-Pad51)") (class "Default")
      (node (ref "BRAIN") (pin "51") (pinfunction "PD12_51") (pintype "bidirectional"))
    )
    (net (code "109") (name "unconnected-(BRAIND-PD20-Pad80)") (class "Default")
      (node (ref "BRAIN") (pin "80") (pinfunction "PD20_80") (pintype "bidirectional"))
    )
    (net (code "110") (name "unconnected-(BRAIND-PD21-Pad81)") (class "Default")
      (node (ref "BRAIN") (pin "81") (pinfunction "PD21_81") (pintype "bidirectional"))
    )
    (net (code "111") (name "unconnected-(BRAINE-VSW-Pad117)") (class "Default")
      (node (ref "BRAIN") (pin "117") (pinfunction "VSW_117") (pintype "bidirectional"))
    )
    (net (code "112") (name "unconnected-(RTC-TS(CLK{slash}INTB)-Pad4)") (class "Default")
      (node (ref "RTC") (pin "4") (pinfunction "TS(CLK/INTB)_4") (pintype "bidirectional"))
    )
    (net (code "113") (name "unconnected-(RTC-~{INTA(CLK})-Pad9)") (class "Default")
      (node (ref "RTC") (pin "9") (pinfunction "~{INTA(CLK})_9") (pintype "bidirectional"))
    )
    (net (code "114") (name "unconnected-(SD-PadDAT1)") (class "Default")
      (node (ref "SD") (pin "DAT1") (pinfunction "DAT1_DAT1") (pintype "bidirectional"))
    )
    (net (code "115") (name "unconnected-(SD-PadDAT2)") (class "Default")
      (node (ref "SD") (pin "DAT2") (pinfunction "DAT2_DAT2") (pintype "bidirectional"))
    )
    (net (code "116") (name "unconnected-(U1-~{HOLD}{slash}SO3-Pad7)") (class "Default")
      (node (ref "U1") (pin "7") (pinfunction "~{HOLD}/SO3_7") (pintype "bidirectional"))
    )
    (net (code "117") (name "unconnected-(U1-~{WP}{slash}SO2-Pad3)") (class "Default")
      (node (ref "U1") (pin "3") (pinfunction "~{WP}/SO2_3") (pintype "bidirectional"))
    )
    (net (code "118") (name "unconnected-(U2-~{HOLD}{slash}SO3-Pad7)") (class "Default")
      (node (ref "U2") (pin "7") (pinfunction "~{HOLD}/SO3_7") (pintype "bidirectional"))
    )
    (net (code "119") (name "unconnected-(U2-~{WP}{slash}SO2-Pad3)") (class "Default")
      (node (ref "U2") (pin "3") (pinfunction "~{WP}/SO2_3") (pintype "bidirectional"))
    )
    (net (code "120") (name "unconnected-(U3-~{HOLD}{slash}SO3-Pad7)") (class "Default")
      (node (ref "U3") (pin "7") (pinfunction "~{HOLD}/SO3_7") (pintype "bidirectional"))
    )
    (net (code "121") (name "unconnected-(U3-~{WP}{slash}SO2-Pad3)") (class "Default")
      (node (ref "U3") (pin "3") (pinfunction "~{WP}/SO2_3") (pintype "bidirectional"))
    )
    (net (code "122") (name "unconnected-(U4-~{HOLD}{slash}SO3-Pad7)") (class "Default")
      (node (ref "U4") (pin "7") (pinfunction "~{HOLD}/SO3_7") (pintype "bidirectional"))
    )
    (net (code "123") (name "unconnected-(U4-~{WP}{slash}SO2-Pad3)") (class "Default")
      (node (ref "U4") (pin "3") (pinfunction "~{WP}/SO2_3") (pintype "bidirectional"))
    )
    (net (code "124") (name "unconnected-(UPPER-PadPIN9)") (class "Default")
      (node (ref "UPPER") (pin "PIN9") (pinfunction "PIN9_PIN9") (pintype "bidirectional"))
    )
    (net (code "125") (name "unconnected-(UPPER-PadPIN13)") (class "Default")
      (node (ref "UPPER") (pin "PIN13") (pinfunction "PIN13_PIN13") (pintype "bidirectional"))
    )
    (net (code "126") (name "unconnected-(UPPER-PadPIN14)") (class "Default")
      (node (ref "UPPER") (pin "PIN14") (pinfunction "PIN14_PIN14") (pintype "bidirectional"))
    )
  )
)
